# Output_Analog.net
KiCad netlist of a schematic drawn in Altium Designer
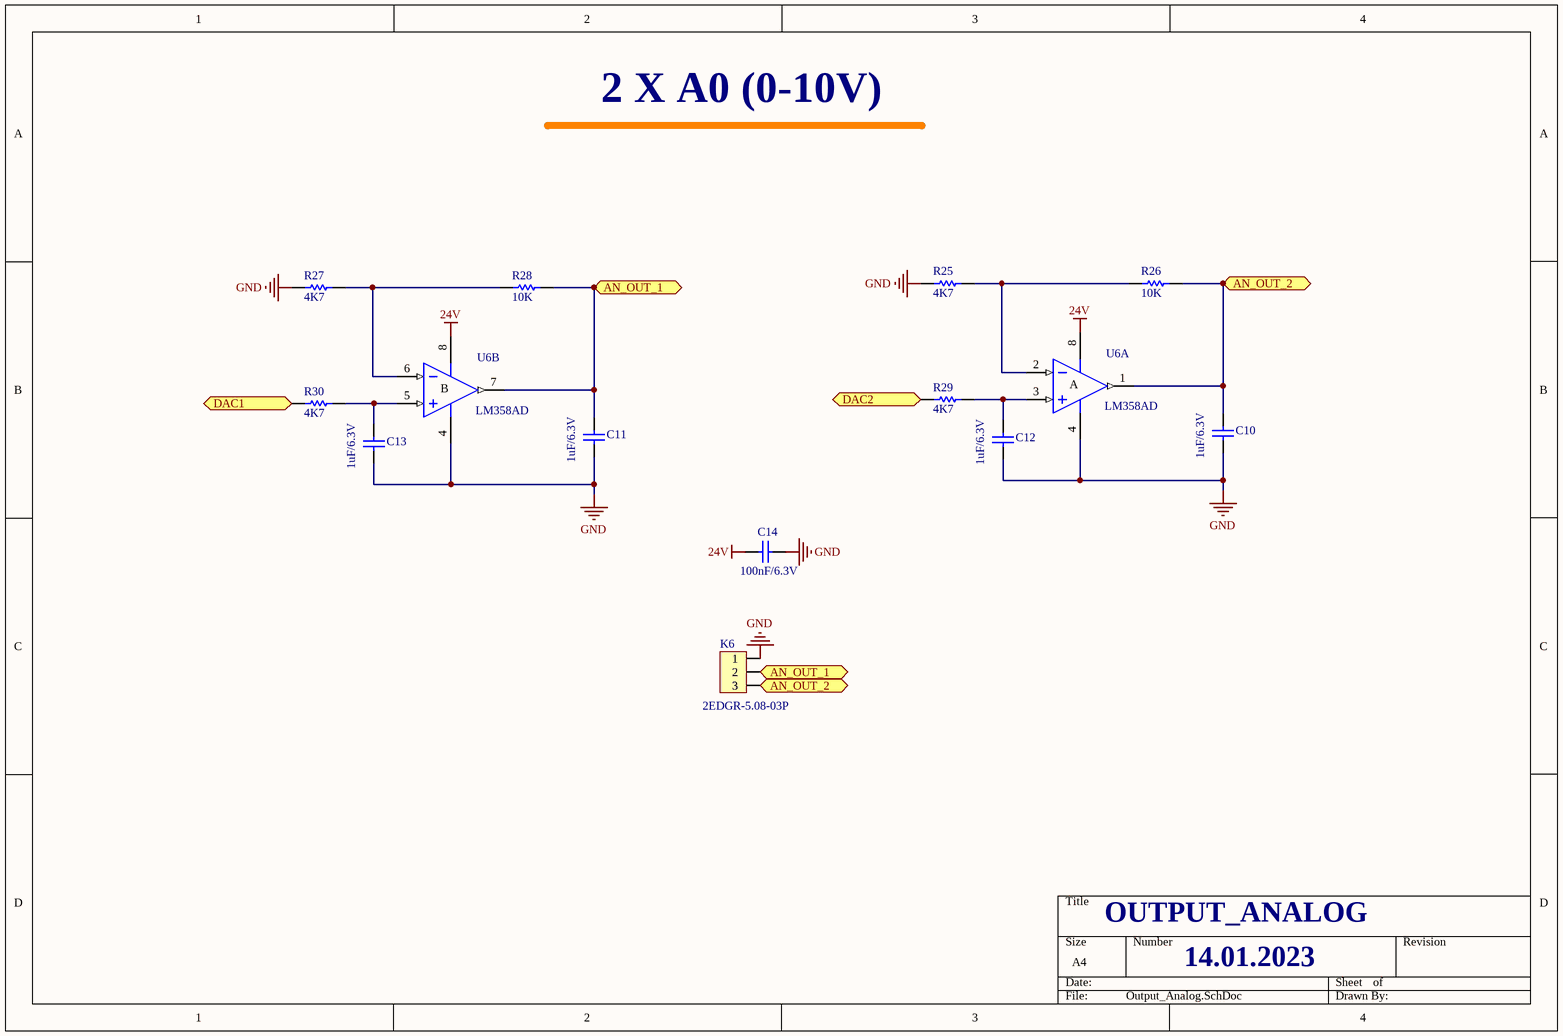
[diagram p0: Output_Analog.SchDoc]

(export (version "E")
  (design (tool "Eeschema 10.0.6"))
  (components
    (comp (ref "C10")
      (value "1uF/6.3V")
      (footprint "CAP0603W")
      (description "CAPACITOR 0603 Case")
      (fields (field (name "PUBLISHER") "Altium Limited"))
      (libsource (lib "geolib") (part "CAP1"))
    )
    (comp (ref "C11")
      (value "1uF/6.3V")
      (footprint "CAP0603W")
      (description "CAPACITOR 0603 Case")
      (fields (field (name "PUBLISHER") "Altium Limited"))
      (libsource (lib "geolib") (part "CAP1"))
    )
    (comp (ref "C12")
      (value "1uF/6.3V")
      (footprint "CAP0603W")
      (description "CAPACITOR 0603 Case")
      (fields (field (name "PUBLISHER") "Altium Limited"))
      (libsource (lib "geolib") (part "CAP1"))
    )
    (comp (ref "C13")
      (value "1uF/6.3V")
      (footprint "CAP0603W")
      (description "CAPACITOR 0603 Case")
      (fields (field (name "PUBLISHER") "Altium Limited"))
      (libsource (lib "geolib") (part "CAP1"))
    )
    (comp (ref "C14")
      (value "100nF/6.3V")
      (footprint "CAP0603W")
      (description "CAPACITOR 0603 Case")
      (fields (field (name "PUBLISHER") "Altium Limited"))
      (libsource (lib "geolib") (part "CAP1"))
    )
    (comp (ref "K6")
      (value "2EDGR-5.08-03P")
      (footprint "CON_DG129_03P")
      (description "CONNECTOR 5.08mm 3PIN 90DEG")
      (libsource (lib "geolib") (part "KLEMENS_3P"))
    )
    (comp (ref "R25")
      (value "4K7")
      (footprint "RES1608[0603]")
      (description "RESISTOR 0603 Case %1")
      (fields (field (name "PUBLISHER") "Altium Limited"))
      (libsource (lib "geolib") (part "RES"))
    )
    (comp (ref "R26")
      (value "10K")
      (footprint "RES1608[0603]")
      (description "RESISTOR 0603 Case %1")
      (fields (field (name "PUBLISHER") "Altium Limited"))
      (libsource (lib "geolib") (part "RES"))
    )
    (comp (ref "R27")
      (value "4K7")
      (footprint "RES1608[0603]")
      (description "RESISTOR 0603 Case %1")
      (fields (field (name "PUBLISHER") "Altium Limited"))
      (libsource (lib "geolib") (part "RES"))
    )
    (comp (ref "R28")
      (value "10K")
      (footprint "RES1608[0603]")
      (description "RESISTOR 0603 Case %1")
      (fields (field (name "PUBLISHER") "Altium Limited"))
      (libsource (lib "geolib") (part "RES"))
    )
    (comp (ref "R29")
      (value "4K7")
      (footprint "RES1608[0603]")
      (description "RESISTOR 0603 Case %1")
      (fields (field (name "PUBLISHER") "Altium Limited"))
      (libsource (lib "geolib") (part "RES"))
    )
    (comp (ref "R30")
      (value "4K7")
      (footprint "RES1608[0603]")
      (description "RESISTOR 0603 Case %1")
      (fields (field (name "PUBLISHER") "Altium Limited"))
      (libsource (lib "geolib") (part "RES"))
    )
    (comp (ref "U6")
      (value "LM358AD")
      (footprint "SO8")
      (description "OPAMP Low-Power Dual Operational Amplifier")
      (fields (field (name "PUBLISHER") "Altium Limited"))
      (libsource (lib "geolib") (part "LM358AD"))
    )
  )
  (nets
    (net (code "1") (name "/AN_OUT_1") (class "Default")
      (node (ref "C11") (pin "2") (pinfunction "2_2") (pintype "passive"))
      (node (ref "K6") (pin "2") (pinfunction "2_2") (pintype "passive"))
      (node (ref "R28") (pin "2") (pinfunction "2_2") (pintype "passive"))
      (node (ref "U6") (pin "7") (pinfunction "OUT_7") (pintype "output"))
    )
    (net (code "2") (name "/AN_OUT_2") (class "Default")
      (node (ref "C10") (pin "2") (pinfunction "2_2") (pintype "passive"))
      (node (ref "K6") (pin "3") (pinfunction "3_3") (pintype "passive"))
      (node (ref "R26") (pin "2") (pinfunction "2_2") (pintype "passive"))
      (node (ref "U6") (pin "1") (pinfunction "OUT_1") (pintype "output"))
    )
    (net (code "3") (name "/DAC1") (class "Default")
      (node (ref "R30") (pin "1") (pinfunction "1_1") (pintype "passive"))
    )
    (net (code "4") (name "/DAC2") (class "Default")
      (node (ref "R29") (pin "1") (pinfunction "1_1") (pintype "passive"))
    )
    (net (code "5") (name "24V") (class "Default")
      (node (ref "C14") (pin "1") (pinfunction "1_1") (pintype "passive"))
      (node (ref "U6") (pin "8") (pinfunction "V+_8") (pintype "power_in"))
    )
    (net (code "6") (name "GND") (class "Default")
      (node (ref "C10") (pin "1") (pinfunction "1_1") (pintype "passive"))
      (node (ref "C11") (pin "1") (pinfunction "1_1") (pintype "passive"))
      (node (ref "C12") (pin "1") (pinfunction "1_1") (pintype "passive"))
      (node (ref "C13") (pin "1") (pinfunction "1_1") (pintype "passive"))
      (node (ref "C14") (pin "2") (pinfunction "2_2") (pintype "passive"))
      (node (ref "K6") (pin "1") (pinfunction "1_1") (pintype "passive"))
      (node (ref "R25") (pin "1") (pinfunction "1_1") (pintype "passive"))
      (node (ref "R27") (pin "1") (pinfunction "1_1") (pintype "passive"))
      (node (ref "U6") (pin "4") (pinfunction "V-_4") (pintype "power_in"))
    )
    (net (code "7") (name "Net-(U6A-IN+)") (class "Default")
      (node (ref "C12") (pin "2") (pinfunction "2_2") (pintype "passive"))
      (node (ref "R29") (pin "2") (pinfunction "2_2") (pintype "passive"))
      (node (ref "U6") (pin "3") (pinfunction "IN+_3") (pintype "input"))
    )
    (net (code "8") (name "Net-(U6A-IN-)") (class "Default")
      (node (ref "R25") (pin "2") (pinfunction "2_2") (pintype "passive"))
      (node (ref "R26") (pin "1") (pinfunction "1_1") (pintype "passive"))
      (node (ref "U6") (pin "2") (pinfunction "IN-_2") (pintype "input"))
    )
    (net (code "9") (name "Net-(U6B-IN+)") (class "Default")
      (node (ref "C13") (pin "2") (pinfunction "2_2") (pintype "passive"))
      (node (ref "R30") (pin "2") (pinfunction "2_2") (pintype "passive"))
      (node (ref "U6") (pin "5") (pinfunction "IN+_5") (pintype "input"))
    )
    (net (code "10") (name "Net-(U6B-IN-)") (class "Default")
      (node (ref "R27") (pin "2") (pinfunction "2_2") (pintype "passive"))
      (node (ref "R28") (pin "1") (pinfunction "1_1") (pintype "passive"))
      (node (ref "U6") (pin "6") (pinfunction "IN-_6") (pintype "input"))
    )
  )
)
